# CPCIS_Connectors_P1_P6.net
KiCad netlist of a schematic drawn in Altium Designer
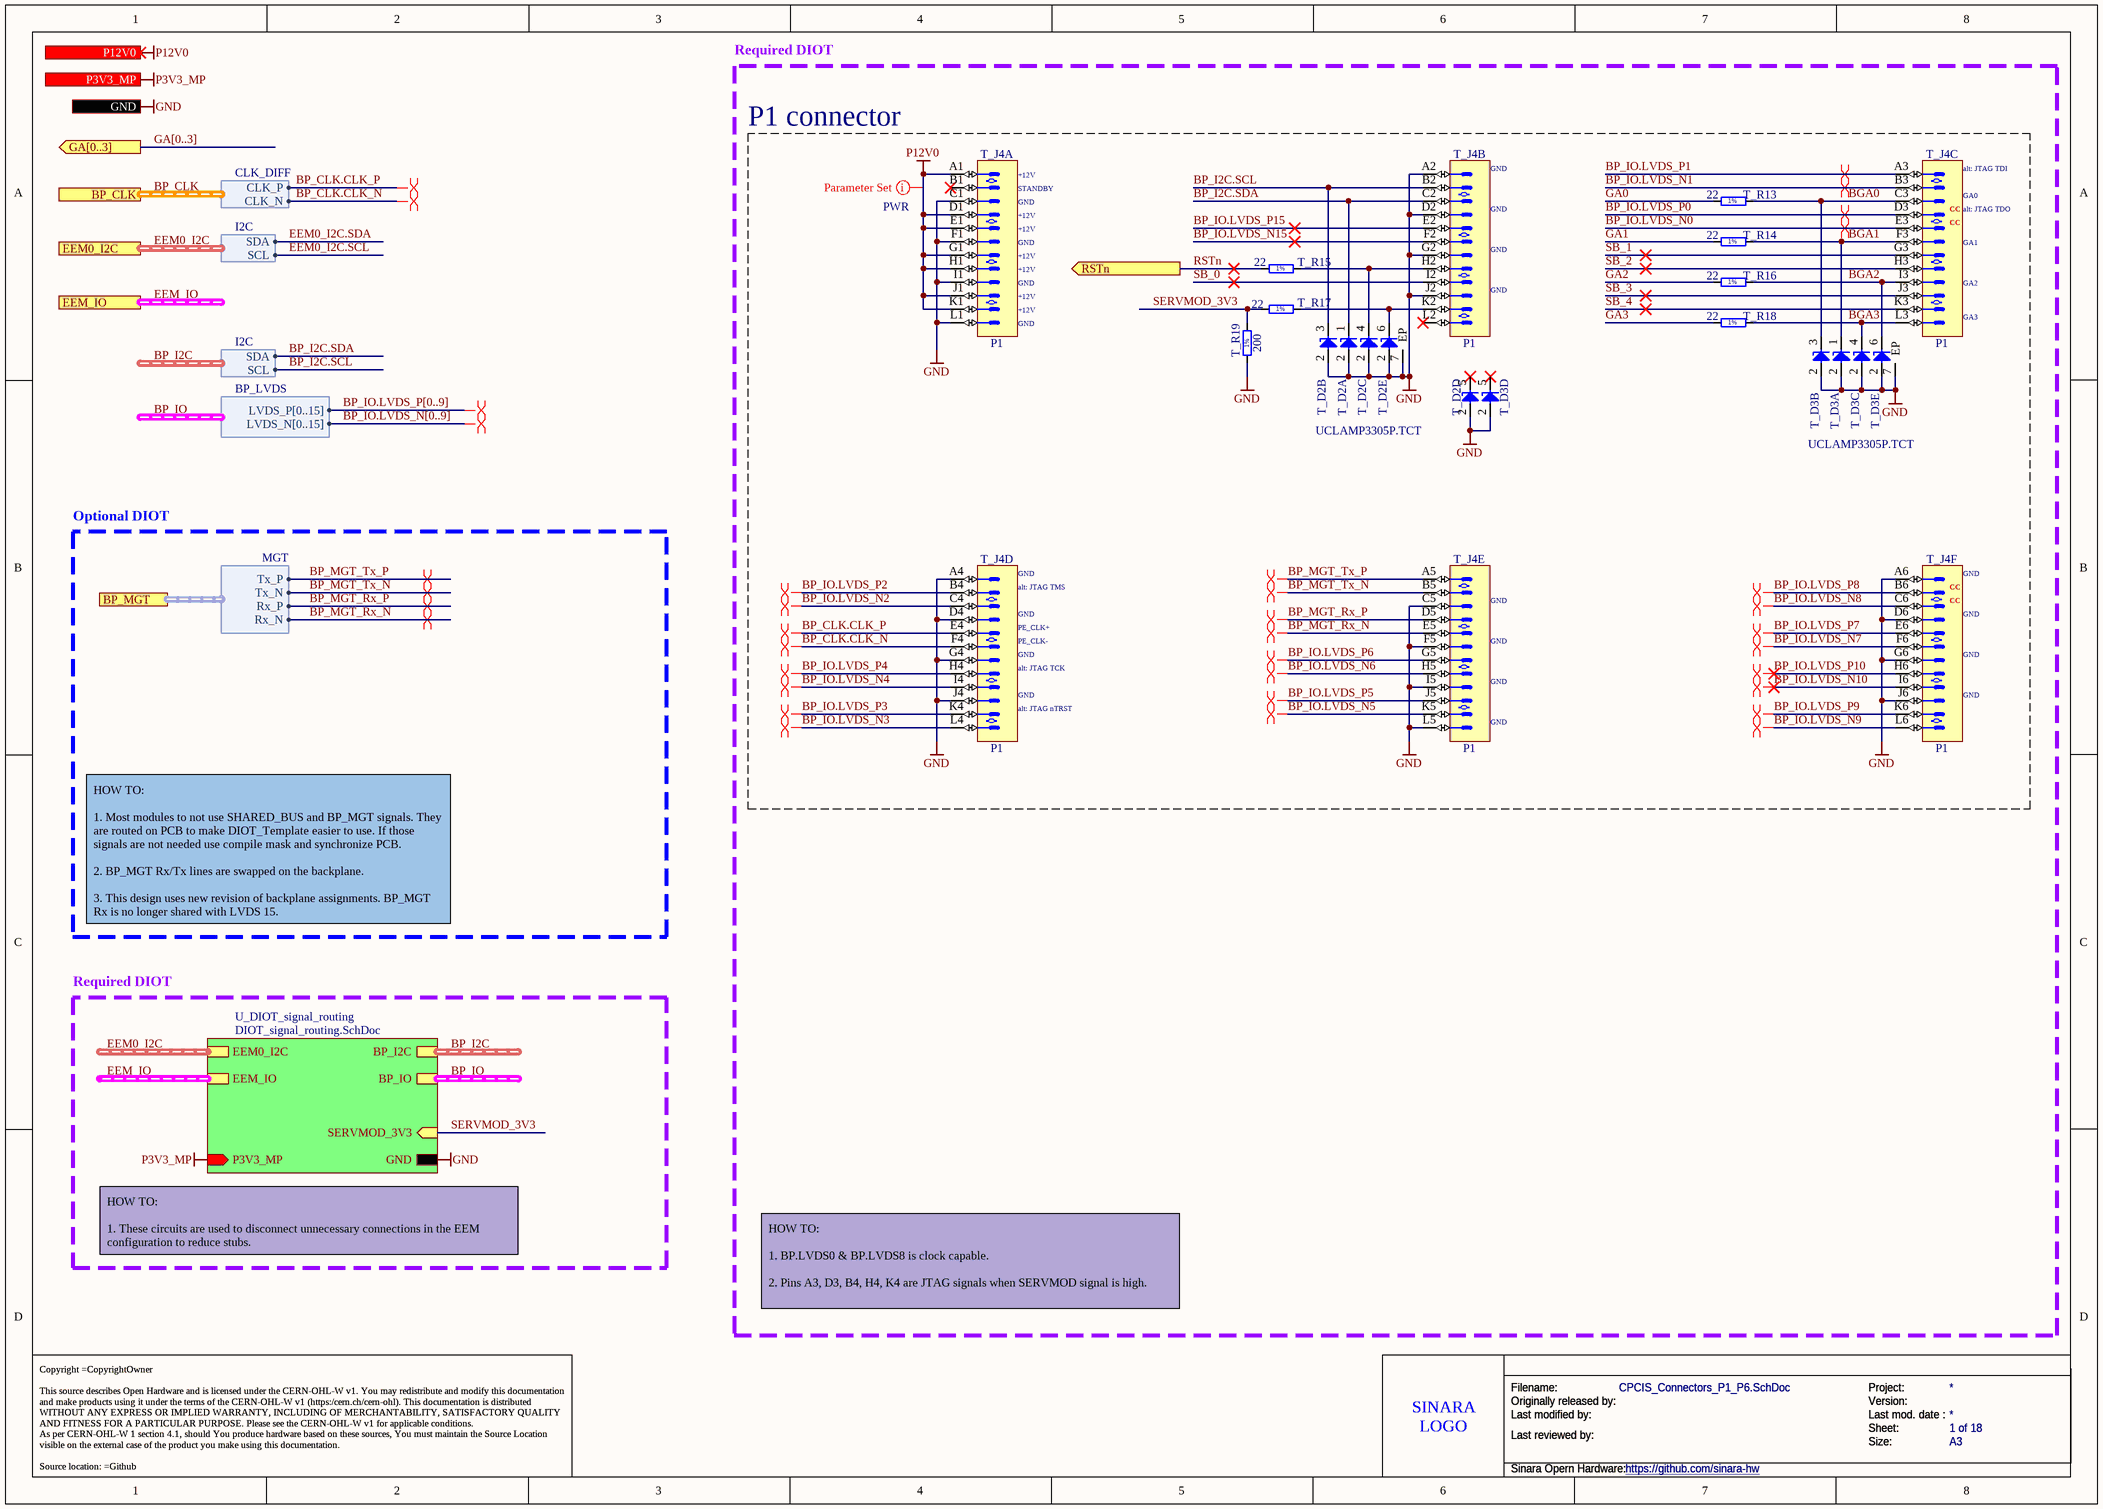
[diagram p0: CPCIS_Connectors_P1_P6.SchDoc]

(export (version "E")
  (design (tool "Eeschema 10.0.6"))
  (components
    (comp (ref "T_D2")
      (value "UCLAMP3305P.TCT")
      (footprint "SON50P160X65_HS-7N")
      (description "Diode TVS Quint Common Anode Uni-Dir 3.3V 40W 6-Pin SLP EP T/R")
      (libsource (lib "TechnoSystem Workspace") (part "D-AK-2"))
    )
    (comp (ref "T_D3")
      (value "UCLAMP3305P.TCT")
      (footprint "SON50P160X65_HS-7N")
      (description "Diode TVS Quint Common Anode Uni-Dir 3.3V 40W 6-Pin SLP EP T/R")
      (libsource (lib "TechnoSystem Workspace") (part "D-AK-2"))
    )
    (comp (ref "T_J4")
      (value "P1")
      (footprint "AMPHENOL_10052825-101LF")
      (description "72 Contacts Header, 6 Columns, 4 Pairs per Column")
      (fields
        (field (name "PART NUMBER") "AMPHENOL_10052825-101LF")
        (field (name "MANUFACTURER") "AMPHENOL")
        (field (name "AUTHOR") "CERN DEM MR")
      )
      (libsource (lib "Connectors") (part "AMPHENOL_10052825-101LF"))
    )
    (comp (ref "T_R13")
      (value "22")
      (footprint "RESC1005X40N")
      (description "Resistor - 1%")
      (fields
        (field (name "PART NUMBER") "R0402_22R_1%_0.0625W_100PPM")
        (field (name "POWER") "0.0625W")
        (field (name "AUTHOR") "CERN DEM JLC")
      )
      (libsource (lib "Resistors") (part "Resistor - 1%"))
    )
    (comp (ref "T_R14")
      (value "22")
      (footprint "RESC1005X40N")
      (description "Resistor - 1%")
      (fields
        (field (name "PART NUMBER") "R0402_22R_1%_0.0625W_100PPM")
        (field (name "POWER") "0.0625W")
        (field (name "AUTHOR") "CERN DEM JLC")
      )
      (libsource (lib "Resistors") (part "Resistor - 1%"))
    )
    (comp (ref "T_R15")
      (value "22")
      (footprint "RESC1005X40N")
      (description "Resistor - 1%")
      (fields
        (field (name "PART NUMBER") "R0402_22R_1%_0.0625W_100PPM")
        (field (name "POWER") "0.0625W")
        (field (name "AUTHOR") "CERN DEM JLC")
      )
      (libsource (lib "Resistors") (part "Resistor - 1%"))
    )
    (comp (ref "T_R16")
      (value "22")
      (footprint "RESC1005X40N")
      (description "Resistor - 1%")
      (fields
        (field (name "PART NUMBER") "R0402_22R_1%_0.0625W_100PPM")
        (field (name "POWER") "0.0625W")
        (field (name "AUTHOR") "CERN DEM JLC")
      )
      (libsource (lib "Resistors") (part "Resistor - 1%"))
    )
    (comp (ref "T_R17")
      (value "22")
      (footprint "RESC1005X40N")
      (description "Resistor - 1%")
      (fields
        (field (name "PART NUMBER") "R0402_22R_1%_0.0625W_100PPM")
        (field (name "POWER") "0.0625W")
        (field (name "AUTHOR") "CERN DEM JLC")
      )
      (libsource (lib "Resistors") (part "Resistor - 1%"))
    )
    (comp (ref "T_R18")
      (value "22")
      (footprint "RESC1005X40N")
      (description "Resistor - 1%")
      (fields
        (field (name "PART NUMBER") "R0402_22R_1%_0.0625W_100PPM")
        (field (name "POWER") "0.0625W")
        (field (name "AUTHOR") "CERN DEM JLC")
      )
      (libsource (lib "Resistors") (part "Resistor - 1%"))
    )
    (comp (ref "T_R19")
      (value "200")
      (footprint "RESC1005X40N")
      (description "Resistor - 1%")
      (fields
        (field (name "PART NUMBER") "R0402_200R_1%_0.0625W_100PPM")
        (field (name "POWER") "0.0625W")
        (field (name "AUTHOR") "CERN DEM JLC")
      )
      (libsource (lib "Resistors") (part "Resistor - 1%"))
    )
  )
  (nets
    (net (code "10") (name "/BGA0") (class "Default")
      (node (ref "T_D3") (pin "3") (pinfunction "C_3") (pintype "passive"))
      (node (ref "T_J4") (pin "C3") (pinfunction "C3_C3") (pintype "bidirectional"))
      (node (ref "T_R13") (pin "2") (pinfunction "2_2") (pintype "passive"))
    )
    (net (code "11") (name "/BGA1") (class "Default")
      (node (ref "T_D3") (pin "1") (pinfunction "C_1") (pintype "passive"))
      (node (ref "T_J4") (pin "F3") (pinfunction "F3_F3") (pintype "bidirectional"))
      (node (ref "T_R14") (pin "2") (pinfunction "2_2") (pintype "passive"))
    )
    (net (code "12") (name "/BGA2") (class "Default")
      (node (ref "T_D3") (pin "6") (pinfunction "C_6") (pintype "passive"))
      (node (ref "T_J4") (pin "I3") (pinfunction "I3_I3") (pintype "bidirectional"))
      (node (ref "T_R16") (pin "2") (pinfunction "2_2") (pintype "passive"))
    )
    (net (code "13") (name "/BGA3") (class "Default")
      (node (ref "T_D3") (pin "4") (pinfunction "C_4") (pintype "passive"))
      (node (ref "T_J4") (pin "L3") (pinfunction "L3_L3") (pintype "bidirectional"))
      (node (ref "T_R18") (pin "2") (pinfunction "2_2") (pintype "passive"))
    )
    (net (code "14") (name "/BP_CLK.CLK_N") (class "Default")
      (node (ref "T_J4") (pin "F4") (pinfunction "F4_F4") (pintype "bidirectional"))
    )
    (net (code "15") (name "/BP_CLK.CLK_P") (class "Default")
      (node (ref "T_J4") (pin "E4") (pinfunction "E4_E4") (pintype "bidirectional"))
    )
    (net (code "17") (name "/BP_I2C.SCL") (class "Default")
      (node (ref "T_D2") (pin "3") (pinfunction "C_3") (pintype "passive"))
      (node (ref "T_J4") (pin "B2") (pinfunction "B2_B2") (pintype "bidirectional"))
    )
    (net (code "18") (name "/BP_I2C.SDA") (class "Default")
      (node (ref "T_D2") (pin "1") (pinfunction "C_1") (pintype "passive"))
      (node (ref "T_J4") (pin "C2") (pinfunction "C2_C2") (pintype "bidirectional"))
    )
    (net (code "20") (name "/BP_IO.LVDS_N0") (class "Default")
      (node (ref "T_J4") (pin "E3") (pinfunction "E3_E3") (pintype "bidirectional"))
    )
    (net (code "21") (name "/BP_IO.LVDS_N1") (class "Default")
      (node (ref "T_J4") (pin "B3") (pinfunction "B3_B3") (pintype "bidirectional"))
    )
    (net (code "22") (name "/BP_IO.LVDS_N2") (class "Default")
      (node (ref "T_J4") (pin "C4") (pinfunction "C4_C4") (pintype "bidirectional"))
    )
    (net (code "23") (name "/BP_IO.LVDS_N3") (class "Default")
      (node (ref "T_J4") (pin "L4") (pinfunction "L4_L4") (pintype "bidirectional"))
    )
    (net (code "24") (name "/BP_IO.LVDS_N4") (class "Default")
      (node (ref "T_J4") (pin "I4") (pinfunction "I4_I4") (pintype "bidirectional"))
    )
    (net (code "25") (name "/BP_IO.LVDS_N5") (class "Default")
      (node (ref "T_J4") (pin "K5") (pinfunction "K5_K5") (pintype "bidirectional"))
    )
    (net (code "26") (name "/BP_IO.LVDS_N6") (class "Default")
      (node (ref "T_J4") (pin "H5") (pinfunction "H5_H5") (pintype "bidirectional"))
    )
    (net (code "27") (name "/BP_IO.LVDS_N7") (class "Default")
      (node (ref "T_J4") (pin "F6") (pinfunction "F6_F6") (pintype "bidirectional"))
    )
    (net (code "28") (name "/BP_IO.LVDS_N8") (class "Default")
      (node (ref "T_J4") (pin "C6") (pinfunction "C6_C6") (pintype "bidirectional"))
    )
    (net (code "29") (name "/BP_IO.LVDS_N9") (class "Default")
      (node (ref "T_J4") (pin "L6") (pinfunction "L6_L6") (pintype "bidirectional"))
    )
    (net (code "30") (name "/BP_IO.LVDS_N10") (class "Default")
      (node (ref "T_J4") (pin "I6") (pinfunction "I6_I6") (pintype "bidirectional+no_connect"))
    )
    (net (code "31") (name "/BP_IO.LVDS_N15") (class "Default")
      (node (ref "T_J4") (pin "F2") (pinfunction "F2_F2") (pintype "bidirectional"))
    )
    (net (code "33") (name "/BP_IO.LVDS_P0") (class "Default")
      (node (ref "T_J4") (pin "D3") (pinfunction "D3_D3") (pintype "bidirectional"))
    )
    (net (code "34") (name "/BP_IO.LVDS_P1") (class "Default")
      (node (ref "T_J4") (pin "A3") (pinfunction "A3_A3") (pintype "bidirectional"))
    )
    (net (code "35") (name "/BP_IO.LVDS_P2") (class "Default")
      (node (ref "T_J4") (pin "B4") (pinfunction "B4_B4") (pintype "bidirectional"))
    )
    (net (code "36") (name "/BP_IO.LVDS_P3") (class "Default")
      (node (ref "T_J4") (pin "K4") (pinfunction "K4_K4") (pintype "bidirectional"))
    )
    (net (code "37") (name "/BP_IO.LVDS_P4") (class "Default")
      (node (ref "T_J4") (pin "H4") (pinfunction "H4_H4") (pintype "bidirectional"))
    )
    (net (code "38") (name "/BP_IO.LVDS_P5") (class "Default")
      (node (ref "T_J4") (pin "J5") (pinfunction "J5_J5") (pintype "bidirectional"))
    )
    (net (code "39") (name "/BP_IO.LVDS_P6") (class "Default")
      (node (ref "T_J4") (pin "G5") (pinfunction "G5_G5") (pintype "bidirectional"))
    )
    (net (code "40") (name "/BP_IO.LVDS_P7") (class "Default")
      (node (ref "T_J4") (pin "E6") (pinfunction "E6_E6") (pintype "bidirectional"))
    )
    (net (code "41") (name "/BP_IO.LVDS_P8") (class "Default")
      (node (ref "T_J4") (pin "B6") (pinfunction "B6_B6") (pintype "bidirectional"))
    )
    (net (code "42") (name "/BP_IO.LVDS_P9") (class "Default")
      (node (ref "T_J4") (pin "K6") (pinfunction "K6_K6") (pintype "bidirectional"))
    )
    (net (code "43") (name "/BP_IO.LVDS_P10") (class "Default")
      (node (ref "T_J4") (pin "H6") (pinfunction "H6_H6") (pintype "bidirectional+no_connect"))
    )
    (net (code "44") (name "/BP_IO.LVDS_P15") (class "Default")
      (node (ref "T_J4") (pin "E2") (pinfunction "E2_E2") (pintype "bidirectional"))
    )
    (net (code "47") (name "/BP_MGT_Rx_N") (class "Default")
      (node (ref "T_J4") (pin "E5") (pinfunction "E5_E5") (pintype "bidirectional"))
    )
    (net (code "48") (name "/BP_MGT_Rx_P") (class "Default")
      (node (ref "T_J4") (pin "D5") (pinfunction "D5_D5") (pintype "bidirectional"))
    )
    (net (code "49") (name "/BP_MGT_Tx_N") (class "Default")
      (node (ref "T_J4") (pin "B5") (pinfunction "B5_B5") (pintype "bidirectional"))
    )
    (net (code "50") (name "/BP_MGT_Tx_P") (class "Default")
      (node (ref "T_J4") (pin "A5") (pinfunction "A5_A5") (pintype "bidirectional"))
    )
    (net (code "54") (name "/GA0") (class "Default")
      (node (ref "T_R13") (pin "1") (pinfunction "1_1") (pintype "passive"))
    )
    (net (code "55") (name "/GA1") (class "Default")
      (node (ref "T_R14") (pin "1") (pinfunction "1_1") (pintype "passive"))
    )
    (net (code "56") (name "/GA2") (class "Default")
      (node (ref "T_R16") (pin "1") (pinfunction "1_1") (pintype "passive"))
    )
    (net (code "57") (name "/GA3") (class "Default")
      (node (ref "T_R18") (pin "1") (pinfunction "1_1") (pintype "passive"))
    )
    (net (code "59") (name "/RSTn") (class "Default")
      (node (ref "T_R15") (pin "1") (pinfunction "1_1") (pintype "passive"))
    )
    (net (code "60") (name "/SB_0") (class "Default")
      (node (ref "T_J4") (pin "I2") (pinfunction "I2_I2") (pintype "bidirectional"))
    )
    (net (code "61") (name "/SB_1") (class "Default")
      (node (ref "T_J4") (pin "G3") (pinfunction "G3_G3") (pintype "bidirectional"))
    )
    (net (code "62") (name "/SB_2") (class "Default")
      (node (ref "T_J4") (pin "H3") (pinfunction "H3_H3") (pintype "bidirectional"))
    )
    (net (code "63") (name "/SB_3") (class "Default")
      (node (ref "T_J4") (pin "J3") (pinfunction "J3_J3") (pintype "bidirectional"))
    )
    (net (code "64") (name "/SB_4") (class "Default")
      (node (ref "T_J4") (pin "K3") (pinfunction "K3_K3") (pintype "bidirectional"))
    )
    (net (code "65") (name "/SERVMOD_3V3") (class "Default")
      (node (ref "T_R17") (pin "1") (pinfunction "1_1") (pintype "passive"))
      (node (ref "T_R19") (pin "2") (pinfunction "2_2") (pintype "passive"))
    )
    (net (code "71") (name "GND") (class "Default")
      (node (ref "T_D2") (pin "2") (pinfunction "A_2") (pintype "passive"))
      (node (ref "T_D2") (pin "7") (pinfunction "EP_7") (pintype "passive"))
      (node (ref "T_D3") (pin "2") (pinfunction "A_2") (pintype "passive"))
      (node (ref "T_D3") (pin "7") (pinfunction "EP_7") (pintype "passive"))
      (node (ref "T_J4") (pin "A2") (pinfunction "A2_A2") (pintype "bidirectional"))
      (node (ref "T_J4") (pin "A4") (pinfunction "A4_A4") (pintype "bidirectional"))
      (node (ref "T_J4") (pin "A6") (pinfunction "A6_A6") (pintype "bidirectional"))
      (node (ref "T_J4") (pin "C1") (pinfunction "C1_C1") (pintype "bidirectional"))
      (node (ref "T_J4") (pin "C5") (pinfunction "C5_C5") (pintype "bidirectional"))
      (node (ref "T_J4") (pin "D2") (pinfunction "D2_D2") (pintype "bidirectional"))
      (node (ref "T_J4") (pin "D4") (pinfunction "D4_D4") (pintype "bidirectional"))
      (node (ref "T_J4") (pin "D6") (pinfunction "D6_D6") (pintype "bidirectional"))
      (node (ref "T_J4") (pin "F1") (pinfunction "F1_F1") (pintype "bidirectional"))
      (node (ref "T_J4") (pin "F5") (pinfunction "F5_F5") (pintype "bidirectional"))
      (node (ref "T_J4") (pin "G2") (pinfunction "G2_G2") (pintype "bidirectional"))
      (node (ref "T_J4") (pin "G4") (pinfunction "G4_G4") (pintype "bidirectional"))
      (node (ref "T_J4") (pin "G6") (pinfunction "G6_G6") (pintype "bidirectional"))
      (node (ref "T_J4") (pin "I1") (pinfunction "I1_I1") (pintype "bidirectional"))
      (node (ref "T_J4") (pin "I5") (pinfunction "I5_I5") (pintype "bidirectional"))
      (node (ref "T_J4") (pin "J2") (pinfunction "J2_J2") (pintype "bidirectional"))
      (node (ref "T_J4") (pin "J4") (pinfunction "J4_J4") (pintype "bidirectional"))
      (node (ref "T_J4") (pin "J6") (pinfunction "J6_J6") (pintype "bidirectional"))
      (node (ref "T_J4") (pin "L1") (pinfunction "L1_L1") (pintype "bidirectional"))
      (node (ref "T_J4") (pin "L5") (pinfunction "L5_L5") (pintype "bidirectional"))
      (node (ref "T_R19") (pin "1") (pinfunction "1_1") (pintype "passive"))
    )
    (net (code "72") (name "Net-(T_D2C-C)") (class "Default")
      (node (ref "T_D2") (pin "4") (pinfunction "C_4") (pintype "passive"))
      (node (ref "T_J4") (pin "H2") (pinfunction "H2_H2") (pintype "bidirectional"))
      (node (ref "T_R15") (pin "2") (pinfunction "2_2") (pintype "passive"))
    )
    (net (code "73") (name "Net-(T_D2E-C)") (class "Default")
      (node (ref "T_D2") (pin "6") (pinfunction "C_6") (pintype "passive"))
      (node (ref "T_J4") (pin "K2") (pinfunction "K2_K2") (pintype "bidirectional"))
      (node (ref "T_R17") (pin "2") (pinfunction "2_2") (pintype "passive"))
    )
    (net (code "75") (name "P12V0") (class "Default")
      (node (ref "T_J4") (pin "A1") (pinfunction "A1_A1") (pintype "bidirectional"))
      (node (ref "T_J4") (pin "D1") (pinfunction "D1_D1") (pintype "bidirectional"))
      (node (ref "T_J4") (pin "E1") (pinfunction "E1_E1") (pintype "bidirectional"))
      (node (ref "T_J4") (pin "G1") (pinfunction "G1_G1") (pintype "bidirectional"))
      (node (ref "T_J4") (pin "H1") (pinfunction "H1_H1") (pintype "bidirectional"))
      (node (ref "T_J4") (pin "J1") (pinfunction "J1_J1") (pintype "bidirectional"))
      (node (ref "T_J4") (pin "K1") (pinfunction "K1_K1") (pintype "bidirectional"))
    )
    (net (code "76") (name "unconnected-(T_D2D-C-Pad5)") (class "Default")
      (node (ref "T_D2") (pin "5") (pinfunction "C_5") (pintype "passive+no_connect"))
    )
    (net (code "77") (name "unconnected-(T_D3D-C-Pad5)") (class "Default")
      (node (ref "T_D3") (pin "5") (pinfunction "C_5") (pintype "passive+no_connect"))
    )
    (net (code "78") (name "unconnected-(T_J4-PadB1)") (class "Default")
      (node (ref "T_J4") (pin "B1") (pinfunction "B1_B1") (pintype "bidirectional+no_connect"))
    )
    (net (code "79") (name "unconnected-(T_J4-PadL2)") (class "Default")
      (node (ref "T_J4") (pin "L2") (pinfunction "L2_L2") (pintype "bidirectional+no_connect"))
    )
  )
)
